# 16X16_-.net
KiCad netlist of a schematic drawn in Altium Designer
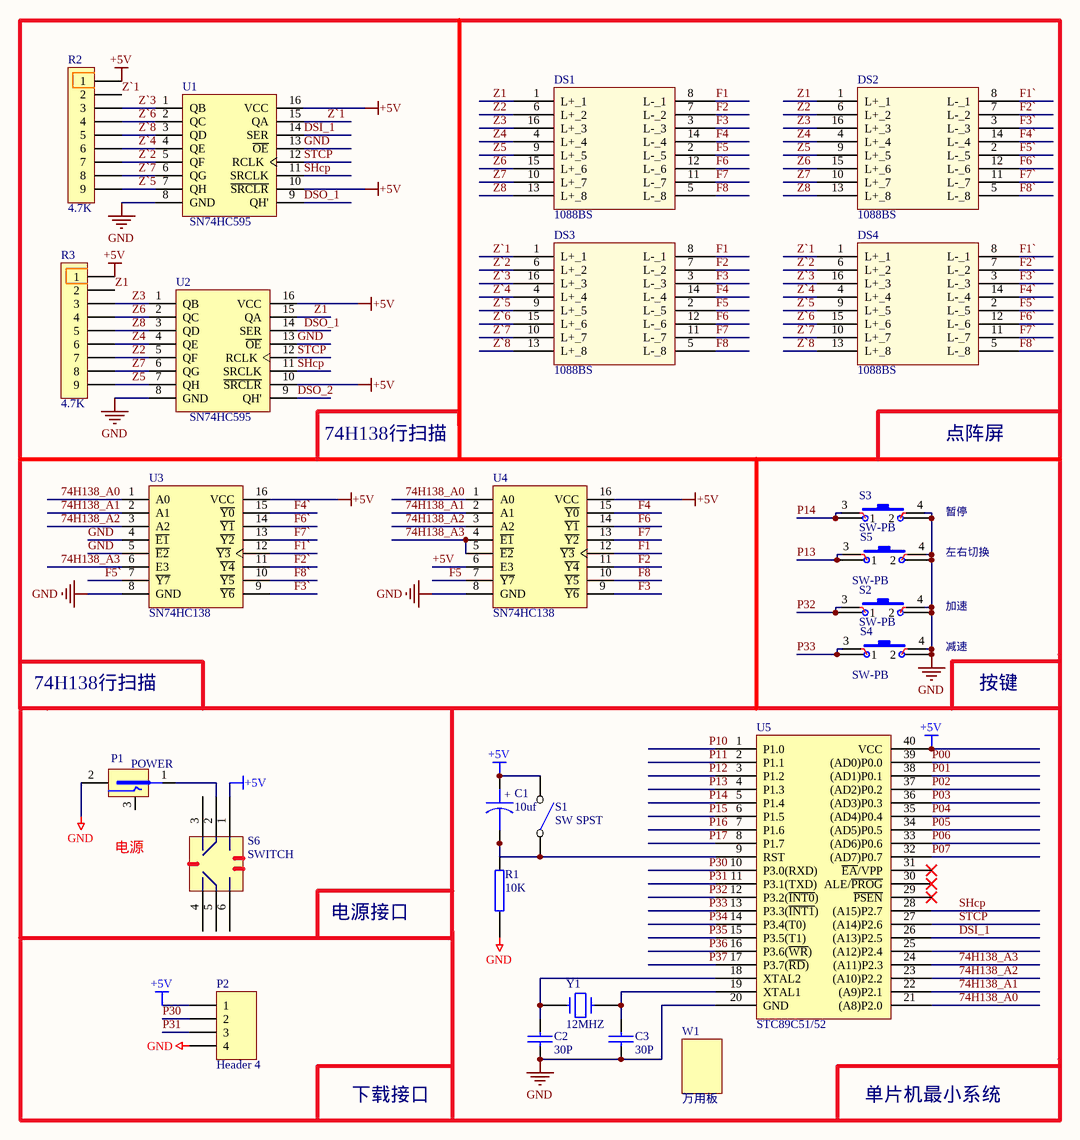
[diagram p0: 16X16点阵显示设计 - 硬件电路.SchDoc]

(export (version "E")
  (design (tool "Eeschema 10.0.6"))
  (components
    (comp (ref "C1")
      (value "10uf")
      (footprint "51单片机毕业设计PCB库:RB-2.54/5MM")
      (description "Capacitor")
      (libsource (lib "*") (part "CAPACITOR POL"))
    )
    (comp (ref "C2")
      (value "30P")
      (footprint "51单片机毕业设计PCB库:CAPR5-4X5")
      (description "Capacitor")
      (libsource (lib "*") (part "CAP"))
    )
    (comp (ref "C3")
      (value "30P")
      (footprint "51单片机毕业设计PCB库:CAPR5-4X5")
      (description "Capacitor")
      (libsource (lib "*") (part "CAP"))
    )
    (comp (ref "DS1")
      (value "1088BS")
      (footprint "点阵显示交通灯设计 - 硬件电路:LEDMatrix")
      (description "LED8*8点阵")
      (libsource (lib "点阵显示交通灯设计 - 硬件电路") (part "LEDMatrix"))
    )
    (comp (ref "DS2")
      (value "1088BS")
      (footprint "点阵显示交通灯设计 - 硬件电路:LEDMatrix")
      (description "LED8*8点阵")
      (libsource (lib "点阵显示交通灯设计 - 硬件电路") (part "LEDMatrix"))
    )
    (comp (ref "DS3")
      (value "1088BS")
      (footprint "点阵显示交通灯设计 - 硬件电路:LEDMatrix")
      (description "LED8*8点阵")
      (libsource (lib "点阵显示交通灯设计 - 硬件电路") (part "LEDMatrix"))
    )
    (comp (ref "DS4")
      (value "1088BS")
      (footprint "点阵显示交通灯设计 - 硬件电路:LEDMatrix")
      (description "LED8*8点阵")
      (libsource (lib "点阵显示交通灯设计 - 硬件电路") (part "LEDMatrix"))
    )
    (comp (ref "P1") (value "POWER") (footprint "51单片机毕业设计PCB库:DC002") (libsource (lib "*") (part "POWER")))
    (comp (ref "P2")
      (value "Header 4")
      (footprint "HDR1X4")
      (description "Header, 4-Pin")
      (fields (field (name "PUBLISHER") "Altium Limited"))
      (libsource (lib "Miscellaneous Connectors") (part "Header 4"))
    )
    (comp (ref "R1") (value "10K") (footprint "51单片机毕业设计PCB库:AXIAL-0.4") (libsource (lib "*") (part "RES2")))
    (comp (ref "R2")
      (value "4.7K")
      (footprint "51单片机毕业设计PCB库:A09")
      (description "9脚排阻")
      (libsource (lib "51单片机毕业设计原理图库") (part "RES_A09"))
    )
    (comp (ref "R3")
      (value "4.7K")
      (footprint "51单片机毕业设计PCB库:A09")
      (description "9脚排阻")
      (libsource (lib "51单片机毕业设计原理图库") (part "RES_A09"))
    )
    (comp (ref "S1")
      (value "SW SPST")
      (footprint "51单片机毕业设计PCB库:SW6*6*5")
      (libsource (lib "*") (part "SW SPST"))
    )
    (comp (ref "S2")
      (value "SW-PB")
      (footprint "51单片机毕业设计PCB库:SW6*6*5")
      (description "按键6X6X5MM")
      (fields (field (name "PUBLISHER") "Altium Limited"))
      (libsource (lib "51单片机毕业设计原理图库") (part "SW-PB"))
    )
    (comp (ref "S3")
      (value "SW-PB")
      (footprint "51单片机毕业设计PCB库:SW6*6*5")
      (description "按键6X6X5MM")
      (fields (field (name "PUBLISHER") "Altium Limited"))
      (libsource (lib "51单片机毕业设计原理图库") (part "SW-PB"))
    )
    (comp (ref "S4")
      (value "SW-PB")
      (footprint "51单片机毕业设计PCB库:SW6*6*5")
      (description "按键6X6X5MM")
      (fields (field (name "PUBLISHER") "Altium Limited"))
      (libsource (lib "51单片机毕业设计原理图库") (part "SW-PB"))
    )
    (comp (ref "S5")
      (value "SW-PB")
      (footprint "51单片机毕业设计PCB库:SW6*6*5")
      (description "按键6X6X5MM")
      (fields (field (name "PUBLISHER") "Altium Limited"))
      (libsource (lib "51单片机毕业设计原理图库") (part "SW-PB"))
    )
    (comp (ref "S6")
      (value "SWITCH")
      (footprint "51单片机毕业设计PCB库:SW6")
      (libsource (lib "51单片机毕业设计原理图库") (part "SWITCH"))
    )
    (comp (ref "U1")
      (value "SN74HC595")
      (footprint "DIP16")
      (description "8-Bit Shift Register with 3-State Output Registers")
      (fields (field (name "PUBLISHER") "Altium Limited"))
      (libsource (lib "51单片机的交通灯设计 - 硬件电路") (part "SN74HC595D"))
    )
    (comp (ref "U2")
      (value "SN74HC595")
      (footprint "DIP16")
      (description "8-Bit Shift Register with 3-State Output Registers")
      (fields (field (name "PUBLISHER") "Altium Limited"))
      (libsource (lib "51单片机的交通灯设计 - 硬件电路") (part "SN74HC595D"))
    )
    (comp (ref "U3")
      (value "SN74HC138")
      (footprint "DIP16")
      (description "8-Bit Shift Register with 3-State Output Registers")
      (fields (field (name "PUBLISHER") "Altium Limited"))
      (libsource (lib "51单片机的交通灯设计 - 硬件电路") (part "SN74HC138"))
    )
    (comp (ref "U4")
      (value "SN74HC138")
      (footprint "DIP16")
      (description "8-Bit Shift Register with 3-State Output Registers")
      (fields (field (name "PUBLISHER") "Altium Limited"))
      (libsource (lib "51单片机的交通灯设计 - 硬件电路") (part "SN74HC138"))
    )
    (comp (ref "U5")
      (value "STC89C51/52")
      (footprint "51单片机毕业设计PCB库:DIP40")
      (description "51单片机")
      (libsource (lib "51单片机毕业设计原理图库") (part "STC89C51"))
    )
    (comp (ref "W1")
      (value "万用板")
      (footprint "51单片机毕业设计PCB库:万能板9X15cm第二版")
      (libsource (lib "51单片机毕业设计原理图库") (part "万用板"))
    )
    (comp (ref "Y1")
      (value "12MHZ")
      (footprint "51单片机毕业设计PCB库:XTAL1")
      (description "Crystal")
      (libsource (lib "*") (part "CRYSTAL"))
    )
  )
  (nets
    (net (code "1") (name "+5V") (class "Default")
      (node (ref "C1") (pin "1") (pinfunction "1_1") (pintype "passive"))
      (node (ref "P2") (pin "1") (pinfunction "1_1") (pintype "passive"))
      (node (ref "R2") (pin "1") (pinfunction "1_1") (pintype "passive"))
      (node (ref "R3") (pin "1") (pinfunction "1_1") (pintype "passive"))
      (node (ref "S1") (pin "2") (pinfunction "NO_2") (pintype "passive"))
      (node (ref "S6") (pin "1") (pinfunction "1_1") (pintype "passive"))
      (node (ref "U1") (pin "10") (pinfunction "~{SRCLR}_10") (pintype "passive"))
      (node (ref "U1") (pin "16") (pinfunction "VCC_16") (pintype "passive"))
      (node (ref "U2") (pin "10") (pinfunction "~{SRCLR}_10") (pintype "passive"))
      (node (ref "U2") (pin "16") (pinfunction "VCC_16") (pintype "passive"))
      (node (ref "U3") (pin "16") (pinfunction "VCC_16") (pintype "passive"))
      (node (ref "U4") (pin "16") (pinfunction "VCC_16") (pintype "passive"))
      (node (ref "U4") (pin "6") (pinfunction "E3_6") (pintype "passive"))
      (node (ref "U5") (pin "40") (pinfunction "VCC_40") (pintype "passive"))
    )
    (net (code "2") (name "/74H138_A0") (class "Default")
      (node (ref "U3") (pin "1") (pinfunction "A0_1") (pintype "passive"))
      (node (ref "U4") (pin "1") (pinfunction "A0_1") (pintype "passive"))
      (node (ref "U5") (pin "21") (pinfunction "(A8)P2.0_21") (pintype "passive"))
    )
    (net (code "3") (name "/74H138_A1") (class "Default")
      (node (ref "U3") (pin "2") (pinfunction "A1_2") (pintype "passive"))
      (node (ref "U4") (pin "2") (pinfunction "A1_2") (pintype "passive"))
      (node (ref "U5") (pin "22") (pinfunction "(A9)P2.1_22") (pintype "passive"))
    )
    (net (code "4") (name "/74H138_A2") (class "Default")
      (node (ref "U3") (pin "3") (pinfunction "A2_3") (pintype "passive"))
      (node (ref "U4") (pin "3") (pinfunction "A2_3") (pintype "passive"))
      (node (ref "U5") (pin "23") (pinfunction "(A10)P2.2_23") (pintype "passive"))
    )
    (net (code "5") (name "/74H138_A3") (class "Default")
      (node (ref "U3") (pin "6") (pinfunction "E3_6") (pintype "passive"))
      (node (ref "U4") (pin "4") (pinfunction "~{E1}_4") (pintype "passive"))
      (node (ref "U4") (pin "5") (pinfunction "~{E2}_5") (pintype "passive"))
      (node (ref "U5") (pin "24") (pinfunction "(A11)P2.3_24") (pintype "passive"))
    )
    (net (code "6") (name "/DSI_1") (class "Default")
      (node (ref "U1") (pin "14") (pinfunction "SER_14") (pintype "passive"))
      (node (ref "U5") (pin "26") (pinfunction "(A13)P2.5_26") (pintype "passive"))
    )
    (net (code "7") (name "/DSO_1") (class "Default")
      (node (ref "U1") (pin "9") (pinfunction "QH'_9") (pintype "passive"))
      (node (ref "U2") (pin "14") (pinfunction "SER_14") (pintype "passive"))
    )
    (net (code "8") (name "/DSO_2") (class "Default")
      (node (ref "U2") (pin "9") (pinfunction "QH'_9") (pintype "passive"))
    )
    (net (code "9") (name "/F1") (class "Default")
      (node (ref "DS1") (pin "8") (pinfunction "L-_1_8") (pintype "passive"))
      (node (ref "DS3") (pin "8") (pinfunction "L-_1_8") (pintype "passive"))
      (node (ref "U4") (pin "12") (pinfunction "~{Y3}_12") (pintype "passive"))
    )
    (net (code "10") (name "/F1`") (class "Default")
      (node (ref "DS2") (pin "8") (pinfunction "L-_1_8") (pintype "passive"))
      (node (ref "DS4") (pin "8") (pinfunction "L-_1_8") (pintype "passive"))
      (node (ref "U3") (pin "12") (pinfunction "~{Y3}_12") (pintype "passive"))
    )
    (net (code "11") (name "/F2") (class "Default")
      (node (ref "DS1") (pin "7") (pinfunction "L-_2_7") (pintype "passive"))
      (node (ref "DS3") (pin "7") (pinfunction "L-_2_7") (pintype "passive"))
      (node (ref "U4") (pin "11") (pinfunction "~{Y4}_11") (pintype "passive"))
    )
    (net (code "12") (name "/F2`") (class "Default")
      (node (ref "DS2") (pin "7") (pinfunction "L-_2_7") (pintype "passive"))
      (node (ref "DS4") (pin "7") (pinfunction "L-_2_7") (pintype "passive"))
      (node (ref "U3") (pin "11") (pinfunction "~{Y4}_11") (pintype "passive"))
    )
    (net (code "13") (name "/F3") (class "Default")
      (node (ref "DS1") (pin "3") (pinfunction "L-_3_3") (pintype "passive"))
      (node (ref "DS3") (pin "3") (pinfunction "L-_3_3") (pintype "passive"))
      (node (ref "U4") (pin "9") (pinfunction "~{Y6}_9") (pintype "passive"))
    )
    (net (code "14") (name "/F3`") (class "Default")
      (node (ref "DS2") (pin "3") (pinfunction "L-_3_3") (pintype "passive"))
      (node (ref "DS4") (pin "3") (pinfunction "L-_3_3") (pintype "passive"))
      (node (ref "U3") (pin "9") (pinfunction "~{Y6}_9") (pintype "passive"))
    )
    (net (code "15") (name "/F4") (class "Default")
      (node (ref "DS1") (pin "14") (pinfunction "L-_4_14") (pintype "passive"))
      (node (ref "DS3") (pin "14") (pinfunction "L-_4_14") (pintype "passive"))
      (node (ref "U4") (pin "15") (pinfunction "~{Y0}_15") (pintype "passive"))
    )
    (net (code "16") (name "/F4`") (class "Default")
      (node (ref "DS2") (pin "14") (pinfunction "L-_4_14") (pintype "passive"))
      (node (ref "DS4") (pin "14") (pinfunction "L-_4_14") (pintype "passive"))
      (node (ref "U3") (pin "15") (pinfunction "~{Y0}_15") (pintype "passive"))
    )
    (net (code "17") (name "/F5") (class "Default")
      (node (ref "DS1") (pin "2") (pinfunction "L-_5_2") (pintype "passive"))
      (node (ref "DS3") (pin "2") (pinfunction "L-_5_2") (pintype "passive"))
      (node (ref "U4") (pin "7") (pinfunction "~{Y7}_7") (pintype "passive"))
    )
    (net (code "18") (name "/F5`") (class "Default")
      (node (ref "DS2") (pin "2") (pinfunction "L-_5_2") (pintype "passive"))
      (node (ref "DS4") (pin "2") (pinfunction "L-_5_2") (pintype "passive"))
      (node (ref "U3") (pin "7") (pinfunction "~{Y7}_7") (pintype "passive"))
    )
    (net (code "19") (name "/F6") (class "Default")
      (node (ref "DS1") (pin "12") (pinfunction "L-_6_12") (pintype "passive"))
      (node (ref "DS3") (pin "12") (pinfunction "L-_6_12") (pintype "passive"))
      (node (ref "U4") (pin "14") (pinfunction "~{Y1}_14") (pintype "passive"))
    )
    (net (code "20") (name "/F6`") (class "Default")
      (node (ref "DS2") (pin "12") (pinfunction "L-_6_12") (pintype "passive"))
      (node (ref "DS4") (pin "12") (pinfunction "L-_6_12") (pintype "passive"))
      (node (ref "U3") (pin "14") (pinfunction "~{Y1}_14") (pintype "passive"))
    )
    (net (code "21") (name "/F7") (class "Default")
      (node (ref "DS1") (pin "11") (pinfunction "L-_7_11") (pintype "passive"))
      (node (ref "DS3") (pin "11") (pinfunction "L-_7_11") (pintype "passive"))
      (node (ref "U4") (pin "13") (pinfunction "~{Y2}_13") (pintype "passive"))
    )
    (net (code "22") (name "/F7`") (class "Default")
      (node (ref "DS2") (pin "11") (pinfunction "L-_7_11") (pintype "passive"))
      (node (ref "DS4") (pin "11") (pinfunction "L-_7_11") (pintype "passive"))
      (node (ref "U3") (pin "13") (pinfunction "~{Y2}_13") (pintype "passive"))
    )
    (net (code "23") (name "/F8") (class "Default")
      (node (ref "DS1") (pin "5") (pinfunction "L-_8_5") (pintype "passive"))
      (node (ref "DS3") (pin "5") (pinfunction "L-_8_5") (pintype "passive"))
      (node (ref "U4") (pin "10") (pinfunction "~{Y5}_10") (pintype "passive"))
    )
    (net (code "24") (name "/F8`") (class "Default")
      (node (ref "DS2") (pin "5") (pinfunction "L-_8_5") (pintype "passive"))
      (node (ref "DS4") (pin "5") (pinfunction "L-_8_5") (pintype "passive"))
      (node (ref "U3") (pin "10") (pinfunction "~{Y5}_10") (pintype "passive"))
    )
    (net (code "25") (name "/P00") (class "Default")
      (node (ref "U5") (pin "39") (pinfunction "(AD0)P0.0_39") (pintype "passive"))
    )
    (net (code "26") (name "/P01") (class "Default")
      (node (ref "U5") (pin "38") (pinfunction "(AD1)P0.1_38") (pintype "passive"))
    )
    (net (code "27") (name "/P02") (class "Default")
      (node (ref "U5") (pin "37") (pinfunction "(AD2)P0.2_37") (pintype "passive"))
    )
    (net (code "28") (name "/P03") (class "Default")
      (node (ref "U5") (pin "36") (pinfunction "(AD3)P0.3_36") (pintype "passive"))
    )
    (net (code "29") (name "/P04") (class "Default")
      (node (ref "U5") (pin "35") (pinfunction "(AD4)P0.4_35") (pintype "passive"))
    )
    (net (code "30") (name "/P05") (class "Default")
      (node (ref "U5") (pin "34") (pinfunction "(AD5)P0.5_34") (pintype "passive"))
    )
    (net (code "31") (name "/P06") (class "Default")
      (node (ref "U5") (pin "33") (pinfunction "(AD6)P0.6_33") (pintype "passive"))
    )
    (net (code "32") (name "/P07") (class "Default")
      (node (ref "U5") (pin "32") (pinfunction "(AD7)P0.7_32") (pintype "passive"))
    )
    (net (code "33") (name "/P10") (class "Default")
      (node (ref "U5") (pin "1") (pinfunction "P1.0_1") (pintype "passive"))
    )
    (net (code "34") (name "/P11") (class "Default")
      (node (ref "U5") (pin "2") (pinfunction "P1.1_2") (pintype "passive"))
    )
    (net (code "35") (name "/P12") (class "Default")
      (node (ref "U5") (pin "3") (pinfunction "P1.2_3") (pintype "passive"))
    )
    (net (code "36") (name "/P13") (class "Default")
      (node (ref "S5") (pin "1") (pinfunction "1_1") (pintype "passive"))
      (node (ref "S5") (pin "3") (pinfunction "3_3") (pintype "passive"))
      (node (ref "U5") (pin "4") (pinfunction "P1.3_4") (pintype "passive"))
    )
    (net (code "37") (name "/P14") (class "Default")
      (node (ref "S3") (pin "1") (pinfunction "1_1") (pintype "passive"))
      (node (ref "S3") (pin "3") (pinfunction "3_3") (pintype "passive"))
      (node (ref "U5") (pin "5") (pinfunction "P1.4_5") (pintype "passive"))
    )
    (net (code "38") (name "/P15") (class "Default")
      (node (ref "U5") (pin "6") (pinfunction "P1.5_6") (pintype "passive"))
    )
    (net (code "39") (name "/P16") (class "Default")
      (node (ref "U5") (pin "7") (pinfunction "P1.6_7") (pintype "passive"))
    )
    (net (code "40") (name "/P17") (class "Default")
      (node (ref "U5") (pin "8") (pinfunction "P1.7_8") (pintype "passive"))
    )
    (net (code "41") (name "/P30") (class "Default")
      (node (ref "P2") (pin "2") (pinfunction "2_2") (pintype "passive"))
      (node (ref "U5") (pin "10") (pinfunction "P3.0(RXD)_10") (pintype "passive"))
    )
    (net (code "42") (name "/P31") (class "Default")
      (node (ref "P2") (pin "3") (pinfunction "3_3") (pintype "passive"))
      (node (ref "U5") (pin "11") (pinfunction "P3.1(TXD)_11") (pintype "passive"))
    )
    (net (code "43") (name "/P32") (class "Default")
      (node (ref "S2") (pin "1") (pinfunction "1_1") (pintype "passive"))
      (node (ref "S2") (pin "3") (pinfunction "3_3") (pintype "passive"))
      (node (ref "U5") (pin "12") (pinfunction "P3.2(~{INT0})_12") (pintype "passive"))
    )
    (net (code "44") (name "/P33") (class "Default")
      (node (ref "S4") (pin "1") (pinfunction "1_1") (pintype "passive"))
      (node (ref "S4") (pin "3") (pinfunction "3_3") (pintype "passive"))
      (node (ref "U5") (pin "13") (pinfunction "P3.3(~{INT1})_13") (pintype "passive"))
    )
    (net (code "45") (name "/P34") (class "Default")
      (node (ref "U5") (pin "14") (pinfunction "P3.4(T0)_14") (pintype "passive"))
    )
    (net (code "46") (name "/P35") (class "Default")
      (node (ref "U5") (pin "15") (pinfunction "P3.5(T1)_15") (pintype "passive"))
    )
    (net (code "47") (name "/P36") (class "Default")
      (node (ref "U5") (pin "16") (pinfunction "P3.6(~{WR})_16") (pintype "passive"))
    )
    (net (code "48") (name "/P37") (class "Default")
      (node (ref "U5") (pin "17") (pinfunction "P3.7(~{RD})_17") (pintype "passive"))
    )
    (net (code "49") (name "/SHcp") (class "Default")
      (node (ref "U1") (pin "11") (pinfunction "SRCLK_11") (pintype "passive"))
      (node (ref "U2") (pin "11") (pinfunction "SRCLK_11") (pintype "passive"))
      (node (ref "U5") (pin "28") (pinfunction "(A15)P2.7_28") (pintype "passive"))
    )
    (net (code "50") (name "/STCP") (class "Default")
      (node (ref "U1") (pin "12") (pinfunction "RCLK_12") (pintype "passive"))
      (node (ref "U2") (pin "12") (pinfunction "RCLK_12") (pintype "passive"))
      (node (ref "U5") (pin "27") (pinfunction "(A14)P2.6_27") (pintype "passive"))
    )
    (net (code "51") (name "/Z1") (class "Default")
      (node (ref "DS1") (pin "1") (pinfunction "L+_1_1") (pintype "passive"))
      (node (ref "DS2") (pin "1") (pinfunction "L+_1_1") (pintype "passive"))
      (node (ref "R3") (pin "2") (pinfunction "2_2") (pintype "passive"))
      (node (ref "U2") (pin "15") (pinfunction "QA_15") (pintype "passive"))
    )
    (net (code "52") (name "/Z2") (class "Default")
      (node (ref "DS1") (pin "6") (pinfunction "L+_2_6") (pintype "passive"))
      (node (ref "DS2") (pin "6") (pinfunction "L+_2_6") (pintype "passive"))
      (node (ref "R3") (pin "7") (pinfunction "7_7") (pintype "passive"))
      (node (ref "U2") (pin "5") (pinfunction "QF_5") (pintype "passive"))
    )
    (net (code "53") (name "/Z3") (class "Default")
      (node (ref "DS1") (pin "16") (pinfunction "L+_3_16") (pintype "passive"))
      (node (ref "DS2") (pin "16") (pinfunction "L+_3_16") (pintype "passive"))
      (node (ref "R3") (pin "3") (pinfunction "3_3") (pintype "passive"))
      (node (ref "U2") (pin "1") (pinfunction "QB_1") (pintype "passive"))
    )
    (net (code "54") (name "/Z4") (class "Default")
      (node (ref "DS1") (pin "4") (pinfunction "L+_4_4") (pintype "passive"))
      (node (ref "DS2") (pin "4") (pinfunction "L+_4_4") (pintype "passive"))
      (node (ref "R3") (pin "6") (pinfunction "6_6") (pintype "passive"))
      (node (ref "U2") (pin "4") (pinfunction "QE_4") (pintype "passive"))
    )
    (net (code "55") (name "/Z5") (class "Default")
      (node (ref "DS1") (pin "9") (pinfunction "L+_5_9") (pintype "passive"))
      (node (ref "DS2") (pin "9") (pinfunction "L+_5_9") (pintype "passive"))
      (node (ref "R3") (pin "9") (pinfunction "9_9") (pintype "passive"))
      (node (ref "U2") (pin "7") (pinfunction "QH_7") (pintype "passive"))
    )
    (net (code "56") (name "/Z6") (class "Default")
      (node (ref "DS1") (pin "15") (pinfunction "L+_6_15") (pintype "passive"))
      (node (ref "DS2") (pin "15") (pinfunction "L+_6_15") (pintype "passive"))
      (node (ref "R3") (pin "4") (pinfunction "4_4") (pintype "passive"))
      (node (ref "U2") (pin "2") (pinfunction "QC_2") (pintype "passive"))
    )
    (net (code "57") (name "/Z7") (class "Default")
      (node (ref "DS1") (pin "10") (pinfunction "L+_7_10") (pintype "passive"))
      (node (ref "DS2") (pin "10") (pinfunction "L+_7_10") (pintype "passive"))
      (node (ref "R3") (pin "8") (pinfunction "8_8") (pintype "passive"))
      (node (ref "U2") (pin "6") (pinfunction "QG_6") (pintype "passive"))
    )
    (net (code "58") (name "/Z8") (class "Default")
      (node (ref "DS1") (pin "13") (pinfunction "L+_8_13") (pintype "passive"))
      (node (ref "DS2") (pin "13") (pinfunction "L+_8_13") (pintype "passive"))
      (node (ref "R3") (pin "5") (pinfunction "5_5") (pintype "passive"))
      (node (ref "U2") (pin "3") (pinfunction "QD_3") (pintype "passive"))
    )
    (net (code "59") (name "/Z`1") (class "Default")
      (node (ref "DS3") (pin "1") (pinfunction "L+_1_1") (pintype "passive"))
      (node (ref "DS4") (pin "1") (pinfunction "L+_1_1") (pintype "passive"))
      (node (ref "R2") (pin "2") (pinfunction "2_2") (pintype "passive"))
      (node (ref "U1") (pin "15") (pinfunction "QA_15") (pintype "passive"))
    )
    (net (code "60") (name "/Z`2") (class "Default")
      (node (ref "DS3") (pin "6") (pinfunction "L+_2_6") (pintype "passive"))
      (node (ref "DS4") (pin "6") (pinfunction "L+_2_6") (pintype "passive"))
      (node (ref "R2") (pin "7") (pinfunction "7_7") (pintype "passive"))
      (node (ref "U1") (pin "5") (pinfunction "QF_5") (pintype "passive"))
    )
    (net (code "61") (name "/Z`3") (class "Default")
      (node (ref "DS3") (pin "16") (pinfunction "L+_3_16") (pintype "passive"))
      (node (ref "DS4") (pin "16") (pinfunction "L+_3_16") (pintype "passive"))
      (node (ref "R2") (pin "3") (pinfunction "3_3") (pintype "passive"))
      (node (ref "U1") (pin "1") (pinfunction "QB_1") (pintype "passive"))
    )
    (net (code "62") (name "/Z`4") (class "Default")
      (node (ref "DS3") (pin "4") (pinfunction "L+_4_4") (pintype "passive"))
      (node (ref "DS4") (pin "4") (pinfunction "L+_4_4") (pintype "passive"))
      (node (ref "R2") (pin "6") (pinfunction "6_6") (pintype "passive"))
      (node (ref "U1") (pin "4") (pinfunction "QE_4") (pintype "passive"))
    )
    (net (code "63") (name "/Z`5") (class "Default")
      (node (ref "DS3") (pin "9") (pinfunction "L+_5_9") (pintype "passive"))
      (node (ref "DS4") (pin "9") (pinfunction "L+_5_9") (pintype "passive"))
      (node (ref "R2") (pin "9") (pinfunction "9_9") (pintype "passive"))
      (node (ref "U1") (pin "7") (pinfunction "QH_7") (pintype "passive"))
    )
    (net (code "64") (name "/Z`6") (class "Default")
      (node (ref "DS3") (pin "15") (pinfunction "L+_6_15") (pintype "passive"))
      (node (ref "DS4") (pin "15") (pinfunction "L+_6_15") (pintype "passive"))
      (node (ref "R2") (pin "4") (pinfunction "4_4") (pintype "passive"))
      (node (ref "U1") (pin "2") (pinfunction "QC_2") (pintype "passive"))
    )
    (net (code "65") (name "/Z`7") (class "Default")
      (node (ref "DS3") (pin "10") (pinfunction "L+_7_10") (pintype "passive"))
      (node (ref "DS4") (pin "10") (pinfunction "L+_7_10") (pintype "passive"))
      (node (ref "R2") (pin "8") (pinfunction "8_8") (pintype "passive"))
      (node (ref "U1") (pin "6") (pinfunction "QG_6") (pintype "passive"))
    )
    (net (code "66") (name "/Z`8") (class "Default")
      (node (ref "DS3") (pin "13") (pinfunction "L+_8_13") (pintype "passive"))
      (node (ref "DS4") (pin "13") (pinfunction "L+_8_13") (pintype "passive"))
      (node (ref "R2") (pin "5") (pinfunction "5_5") (pintype "passive"))
      (node (ref "U1") (pin "3") (pinfunction "QD_3") (pintype "passive"))
    )
    (net (code "67") (name "GND") (class "Default")
      (node (ref "C2") (pin "1") (pinfunction "1_1") (pintype "passive"))
      (node (ref "C3") (pin "1") (pinfunction "1_1") (pintype "passive"))
      (node (ref "P1") (pin "2") (pintype "passive"))
      (node (ref "P2") (pin "4") (pinfunction "4_4") (pintype "passive"))
      (node (ref "R1") (pin "1") (pinfunction "1_1") (pintype "passive"))
      (node (ref "S2") (pin "2") (pinfunction "2_2") (pintype "passive"))
      (node (ref "S2") (pin "4") (pinfunction "4_4") (pintype "passive"))
      (node (ref "S3") (pin "2") (pinfunction "2_2") (pintype "passive"))
      (node (ref "S3") (pin "4") (pinfunction "4_4") (pintype "passive"))
      (node (ref "S4") (pin "2") (pinfunction "2_2") (pintype "passive"))
      (node (ref "S4") (pin "4") (pinfunction "4_4") (pintype "passive"))
      (node (ref "S5") (pin "2") (pinfunction "2_2") (pintype "passive"))
      (node (ref "S5") (pin "4") (pinfunction "4_4") (pintype "passive"))
      (node (ref "U1") (pin "13") (pinfunction "~{OE}_13") (pintype "passive"))
      (node (ref "U1") (pin "8") (pinfunction "GND_8") (pintype "passive"))
      (node (ref "U2") (pin "13") (pinfunction "~{OE}_13") (pintype "passive"))
      (node (ref "U2") (pin "8") (pinfunction "GND_8") (pintype "passive"))
      (node (ref "U3") (pin "4") (pinfunction "~{E1}_4") (pintype "passive"))
      (node (ref "U3") (pin "5") (pinfunction "~{E2}_5") (pintype "passive"))
      (node (ref "U3") (pin "8") (pinfunction "GND_8") (pintype "passive"))
      (node (ref "U4") (pin "8") (pinfunction "GND_8") (pintype "passive"))
      (node (ref "U5") (pin "20") (pinfunction "GND_20") (pintype "passive"))
    )
    (net (code "68") (name "Net-(P1-Pad1)") (class "Default")
      (node (ref "P1") (pin "1") (pintype "passive"))
      (node (ref "S6") (pin "2") (pinfunction "2_2") (pintype "passive"))
    )
    (net (code "69") (name "Net-(S1-COMMON)") (class "Default")
      (node (ref "C1") (pin "2") (pinfunction "2_2") (pintype "passive"))
      (node (ref "R1") (pin "2") (pinfunction "2_2") (pintype "passive"))
      (node (ref "S1") (pin "1") (pinfunction "COMMON_1") (pintype "passive"))
      (node (ref "U5") (pin "9") (pinfunction "RST_9") (pintype "passive"))
    )
    (net (code "70") (name "Net-(U5-XTAL1)") (class "Default")
      (node (ref "C3") (pin "2") (pinfunction "2_2") (pintype "passive"))
      (node (ref "U5") (pin "19") (pinfunction "XTAL1_19") (pintype "passive"))
      (node (ref "Y1") (pin "2") (pinfunction "2_2") (pintype "passive"))
    )
    (net (code "71") (name "Net-(U5-XTAL2)") (class "Default")
      (node (ref "C2") (pin "2") (pinfunction "2_2") (pintype "passive"))
      (node (ref "U5") (pin "18") (pinfunction "XTAL2_18") (pintype "passive"))
      (node (ref "Y1") (pin "1") (pinfunction "1_1") (pintype "passive"))
    )
    (net (code "72") (name "unconnected-(P1-Pad3)") (class "Default")
      (node (ref "P1") (pin "3") (pintype "passive"))
    )
    (net (code "73") (name "unconnected-(S6-Pad3)") (class "Default")
      (node (ref "S6") (pin "3") (pinfunction "3_3") (pintype "passive"))
    )
    (net (code "74") (name "unconnected-(S6-Pad4)") (class "Default")
      (node (ref "S6") (pin "4") (pinfunction "4_4") (pintype "passive"))
    )
    (net (code "75") (name "unconnected-(S6-Pad5)") (class "Default")
      (node (ref "S6") (pin "5") (pinfunction "5_5") (pintype "passive"))
    )
    (net (code "76") (name "unconnected-(S6-Pad6)") (class "Default")
      (node (ref "S6") (pin "6") (pinfunction "6_6") (pintype "passive"))
    )
    (net (code "77") (name "unconnected-(U5-(A12)P2.4-Pad25)") (class "Default")
      (node (ref "U5") (pin "25") (pinfunction "(A12)P2.4_25") (pintype "passive"))
    )
    (net (code "78") (name "unconnected-(U5-ALE{slash}~{PROG}-Pad30)") (class "Default")
      (node (ref "U5") (pin "30") (pinfunction "ALE/~{PROG}_30") (pintype "passive+no_connect"))
    )
    (net (code "79") (name "unconnected-(U5-~{EA}{slash}VPP-Pad31)") (class "Default")
      (node (ref "U5") (pin "31") (pinfunction "~{EA}/VPP_31") (pintype "passive+no_connect"))
    )
    (net (code "80") (name "unconnected-(U5-~{PSEN}-Pad29)") (class "Default")
      (node (ref "U5") (pin "29") (pinfunction "~{PSEN}_29") (pintype "passive+no_connect"))
    )
  )
)
